# FanDriver.net
KiCad netlist of a schematic drawn in EAGLE
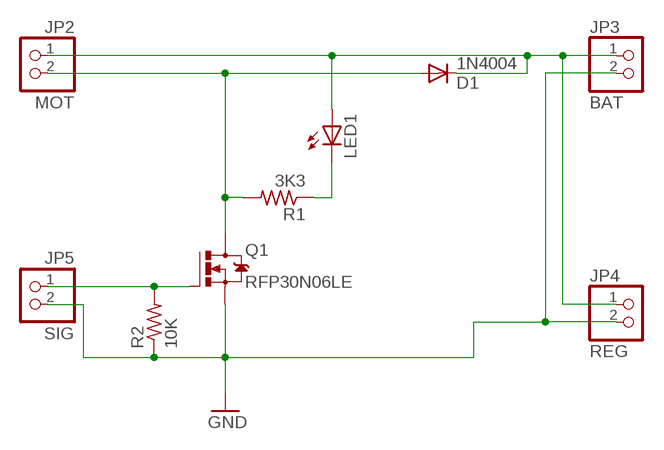
[diagram p0: schematic, sheet 1]

(export (version "E")
  (design (tool "Eeschema 10.0.6"))
  (components
    (comp (ref "D1")
      (value "1N4004")
      (footprint "eagle-import:DO41-10")
      (libsource (lib "eagle-import") (part "1N4004"))
    )
    (comp (ref "JP2")
      (value "MOT")
      (footprint "eagle-import:1X02-S")
      (libsource (lib "eagle-import") (part "PINHD-1X02_2.54-S"))
    )
    (comp (ref "JP3")
      (value "BAT")
      (footprint "eagle-import:1X02-S")
      (libsource (lib "eagle-import") (part "PINHD-1X02_2.54-S"))
    )
    (comp (ref "JP4")
      (value "REG")
      (footprint "eagle-import:1X02-S")
      (libsource (lib "eagle-import") (part "PINHD-1X02_2.54-S"))
    )
    (comp (ref "JP5")
      (value "SIG")
      (footprint "eagle-import:1X02-S")
      (libsource (lib "eagle-import") (part "PINHD-1X02_2.54-S"))
    )
    (comp (ref "LED1")
      (value "LEDCHIPLED_1206")
      (footprint "eagle-import:CHIPLED_1206")
      (libsource (lib "eagle-import") (part "LEDCHIPLED_1206"))
    )
    (comp (ref "Q1")
      (value "RFP30N06LE")
      (footprint "eagle-import:TO220BV")
      (libsource (lib "eagle-import") (part "MOSFET-NBV"))
    )
    (comp (ref "R1")
      (value "3K3")
      (footprint "eagle-import:R0603")
      (libsource (lib "eagle-import") (part "R-US_R0603"))
    )
    (comp (ref "R2")
      (value "10K")
      (footprint "eagle-import:R0603")
      (libsource (lib "eagle-import") (part "R-US_R0603"))
    )
  )
  (nets
    (net (code "1") (name "GND") (class "Default")
      (node (ref "JP3") (pin "2") (pinfunction "2_2") (pintype "passive"))
      (node (ref "JP4") (pin "2") (pinfunction "2_2") (pintype "passive"))
      (node (ref "JP5") (pin "2") (pinfunction "2_2") (pintype "passive"))
      (node (ref "Q1") (pin "S") (pinfunction "S_S") (pintype "passive"))
      (node (ref "R2") (pin "1") (pinfunction "1_1") (pintype "passive"))
    )
    (net (code "2") (name "Net-(D1-PadA)") (class "Default")
      (node (ref "D1") (pin "A") (pinfunction "A_A") (pintype "passive"))
      (node (ref "JP2") (pin "2") (pinfunction "2_2") (pintype "passive"))
      (node (ref "Q1") (pin "D") (pinfunction "D_D") (pintype "passive"))
      (node (ref "R1") (pin "2") (pinfunction "2_2") (pintype "passive"))
    )
    (net (code "3") (name "Net-(D1-PadC)") (class "Default")
      (node (ref "D1") (pin "C") (pinfunction "C_C") (pintype "passive"))
      (node (ref "JP2") (pin "1") (pinfunction "1_1") (pintype "passive"))
      (node (ref "JP3") (pin "1") (pinfunction "1_1") (pintype "passive"))
      (node (ref "JP4") (pin "1") (pinfunction "1_1") (pintype "passive"))
      (node (ref "LED1") (pin "A") (pinfunction "A_A") (pintype "passive"))
    )
    (net (code "4") (name "Net-(JP5-Pad1)") (class "Default")
      (node (ref "JP5") (pin "1") (pinfunction "1_1") (pintype "passive"))
      (node (ref "Q1") (pin "G") (pinfunction "G_G") (pintype "passive"))
      (node (ref "R2") (pin "2") (pinfunction "2_2") (pintype "passive"))
    )
    (net (code "5") (name "Net-(LED1-PadC)") (class "Default")
      (node (ref "LED1") (pin "C") (pinfunction "C_C") (pintype "passive"))
      (node (ref "R1") (pin "1") (pinfunction "1_1") (pintype "passive"))
    )
  )
)
